# Fan_driver.net
KiCad netlist of a schematic drawn in Altium Designer
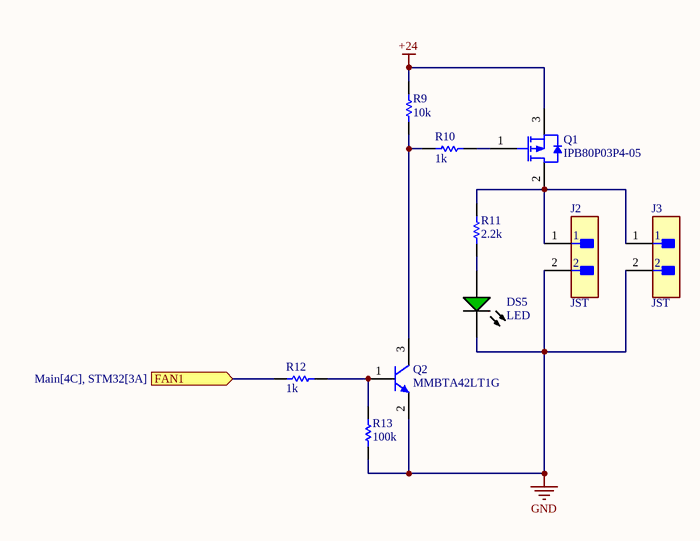
[diagram p0: Fan_driver.SchDoc]

(export (version "E")
  (design (tool "Eeschema 10.0.6"))
  (components
    (comp (ref "DS5")
      (value "LED")
      (footprint "AVAG-HSMX-C170_V")
      (description "Chip LED, Green, 2.2 V, -40 to 85 degC, 2-Pin SMD, Pb-Free, Tape and Reel")
      (fields (field (name "MANUFACTURER") "Avago"))
      (libsource (lib "Altium Content Vault") (part "LED_GREEN_A1K2-2"))
    )
    (comp (ref "J2")
      (value "JST")
      (footprint "FP-B2B-EH-A_LF_SN-MFG")
      (description "CONN HEADER VERT 2POS 2.5MM")
      (libsource (lib "Altium Content Vault") (part "3bc925449376181038e59eaffc5286c"))
    )
    (comp (ref "J3")
      (value "JST")
      (footprint "FP-B2B-EH-A_LF_SN-MFG")
      (description "CONN HEADER VERT 2POS 2.5MM")
      (libsource (lib "Altium Content Vault") (part "3bc925449376181038e59eaffc5286c"))
    )
    (comp (ref "Q1")
      (value "IPB80P03P4-05")
      (footprint "INF-PG-TO263-3-2_N")
      (description "OptiMOS-P2 Power-Transistor, -30 V VDS, -80 A ID, PG-TO263-3-2, Reel, Green")
      (fields (field (name "MANUFACTURER") "Infineon"))
      (libsource (lib "Altium Content Vault") (part "INF-MOSFET-P-3"))
    )
    (comp (ref "Q2")
      (value "MMBTA42LT1G")
      (footprint "ONSC-SOT-23-3-318-08_V")
      (description "High Voltage Transistor, NPN Silicon, 3-Pin SOT-23, Pb-Free, Tape and Reel")
      (fields (field (name "MANUFACTURER") "On Semiconductor"))
      (libsource (lib "Altium Content Vault") (part "ONSC-NPN-B1E2C3-3"))
    )
    (comp (ref "R9")
      (value "10k")
      (footprint "RESC2013X50X30LL20T20")
      (fields (field (name "MANUFACTURER") "Vishay Dale") (field (name "PART NUMBER") "CRCW08050000Z0EA"))
      (libsource (lib "Altium Content Vault") (part "RES"))
    )
    (comp (ref "R10")
      (value "1k")
      (footprint "RESC2013X50X30LL20T20")
      (fields (field (name "MANUFACTURER") "Vishay Dale") (field (name "PART NUMBER") "CRCW08050000Z0EA"))
      (libsource (lib "Altium Content Vault") (part "RES"))
    )
    (comp (ref "R11")
      (value "2.2k")
      (footprint "RESC2013X50X30LL20T20")
      (fields (field (name "MANUFACTURER") "Vishay Dale") (field (name "PART NUMBER") "CRCW08050000Z0EA"))
      (libsource (lib "Altium Content Vault") (part "RES"))
    )
    (comp (ref "R12")
      (value "1k")
      (footprint "RESC2013X50X30LL20T20")
      (fields (field (name "MANUFACTURER") "Vishay Dale") (field (name "PART NUMBER") "CRCW08050000Z0EA"))
      (libsource (lib "Altium Content Vault") (part "RES"))
    )
    (comp (ref "R13")
      (value "100k")
      (footprint "RESC2013X50X30LL20T20")
      (fields (field (name "MANUFACTURER") "Vishay Dale") (field (name "PART NUMBER") "CRCW08050000Z0EA"))
      (libsource (lib "Altium Content Vault") (part "RES"))
    )
  )
  (nets
    (net (code "1") (name "+24") (class "Default")
      (node (ref "Q1") (pin "3") (pinfunction "SOURCE_3") (pintype "passive"))
      (node (ref "R9") (pin "2") (pinfunction "2_2") (pintype "passive"))
    )
    (net (code "2") (name "/FAN1") (class "Default")
      (node (ref "R12") (pin "1") (pinfunction "1_1") (pintype "passive"))
    )
    (net (code "3") (name "GND") (class "Default")
      (node (ref "DS5") (pin "2") (pinfunction "K_2") (pintype "passive"))
      (node (ref "J2") (pin "2") (pinfunction "2_2") (pintype "passive"))
      (node (ref "J3") (pin "2") (pinfunction "2_2") (pintype "passive"))
      (node (ref "Q2") (pin "2") (pinfunction "E_2") (pintype "passive"))
      (node (ref "R13") (pin "1") (pinfunction "1_1") (pintype "passive"))
    )
    (net (code "4") (name "Net-(DS5-A)") (class "Default")
      (node (ref "DS5") (pin "1") (pinfunction "A_1") (pintype "passive"))
      (node (ref "R11") (pin "1") (pinfunction "1_1") (pintype "passive"))
    )
    (net (code "5") (name "Net-(Q1-DRAIN)") (class "Default")
      (node (ref "J2") (pin "1") (pinfunction "1_1") (pintype "passive"))
      (node (ref "J3") (pin "1") (pinfunction "1_1") (pintype "passive"))
      (node (ref "Q1") (pin "2") (pinfunction "DRAIN_2") (pintype "passive"))
      (node (ref "R11") (pin "2") (pinfunction "2_2") (pintype "passive"))
    )
    (net (code "6") (name "Net-(Q1-GATE)") (class "Default")
      (node (ref "Q1") (pin "1") (pinfunction "GATE_1") (pintype "passive"))
      (node (ref "R10") (pin "2") (pinfunction "2_2") (pintype "passive"))
    )
    (net (code "7") (name "Net-(Q2-B)") (class "Default")
      (node (ref "Q2") (pin "1") (pinfunction "B_1") (pintype "passive"))
      (node (ref "R12") (pin "2") (pinfunction "2_2") (pintype "passive"))
      (node (ref "R13") (pin "2") (pinfunction "2_2") (pintype "passive"))
    )
    (net (code "8") (name "Net-(Q2-C)") (class "Default")
      (node (ref "Q2") (pin "3") (pinfunction "C_3") (pintype "passive"))
      (node (ref "R10") (pin "1") (pinfunction "1_1") (pintype "passive"))
      (node (ref "R9") (pin "1") (pinfunction "1_1") (pintype "passive"))
    )
  )
)
